# 2023-08-03_LVMi_Thermistors.net
KiCad netlist of a schematic drawn in EAGLE
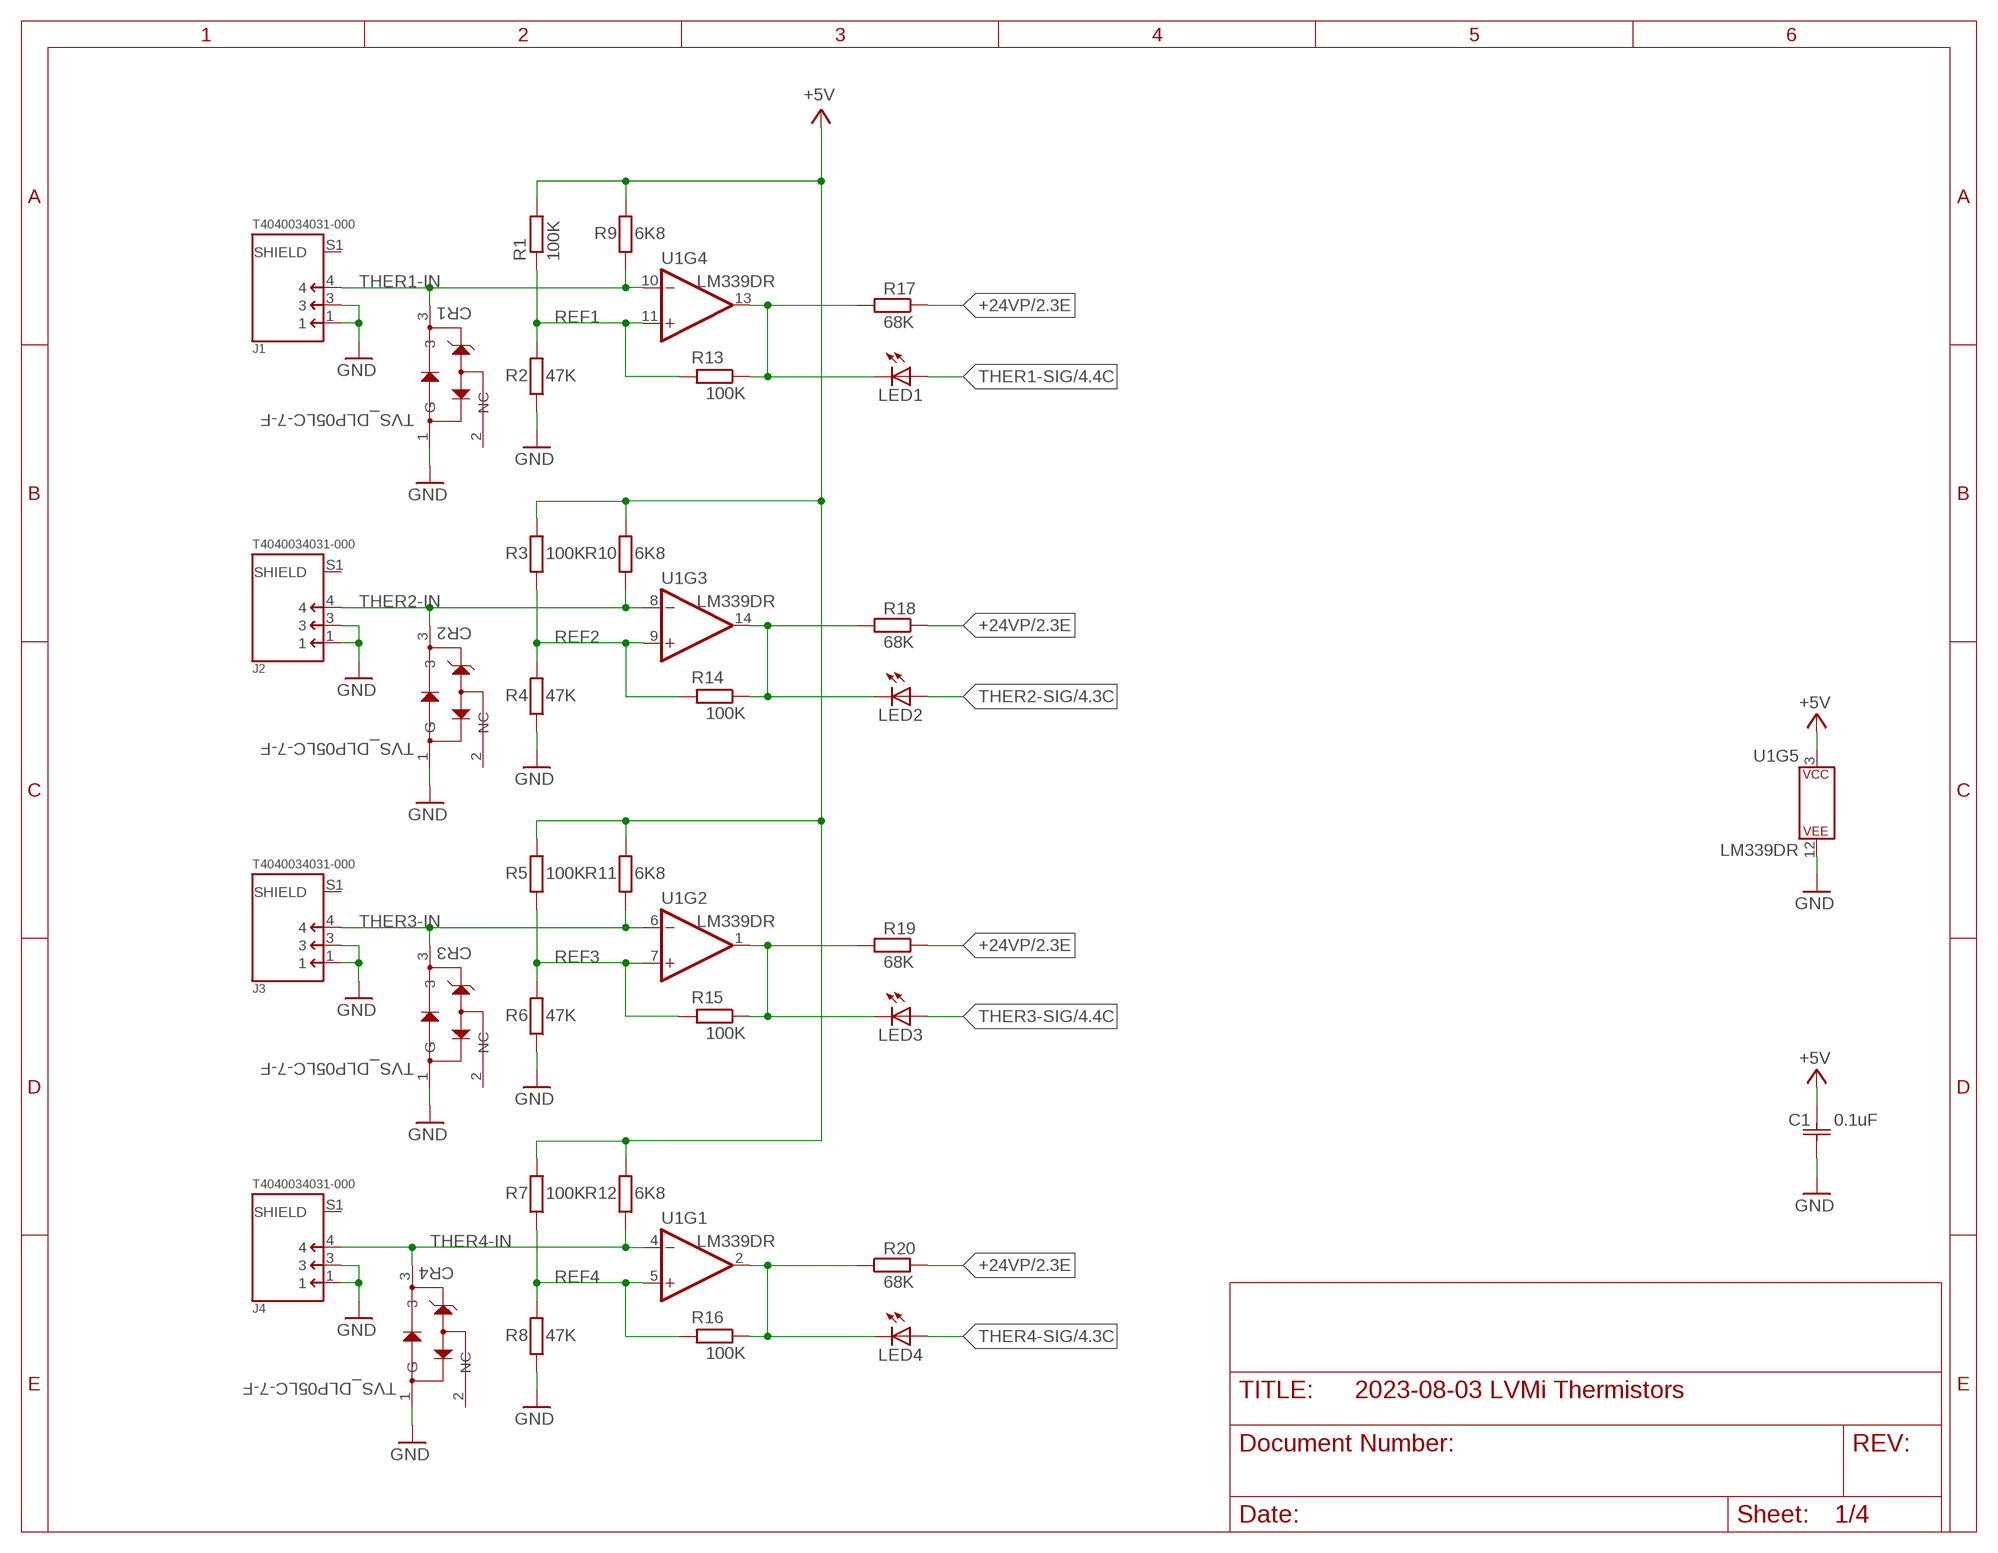
[diagram p0: schematic, sheet 1]
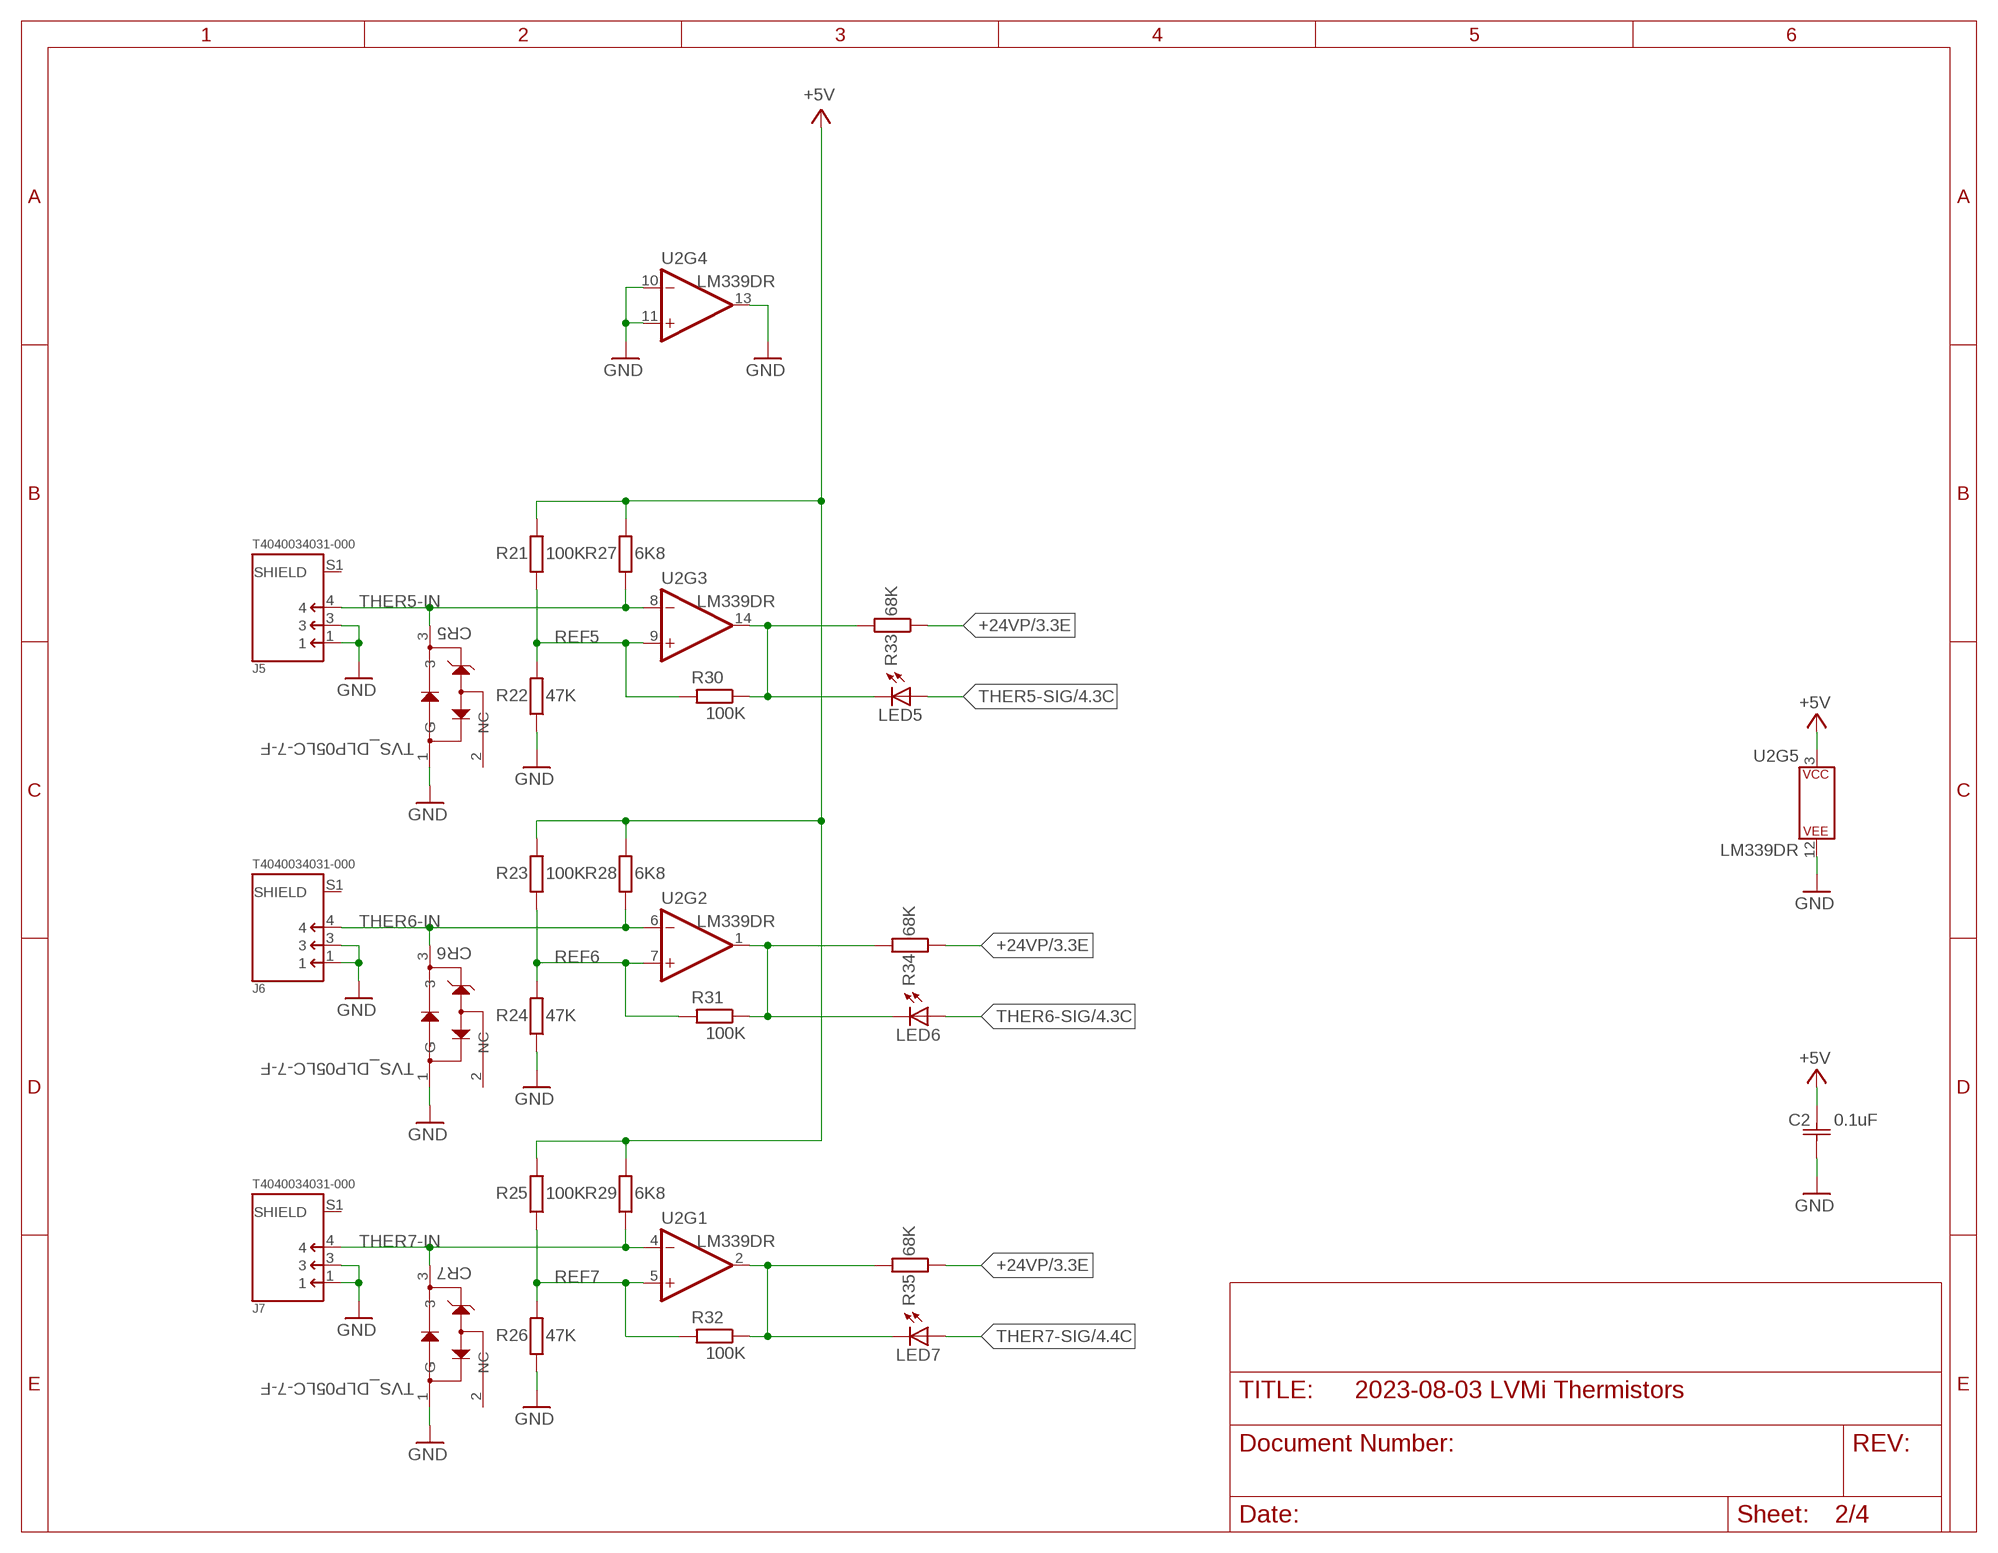
[diagram p1: schematic, sheet 2]
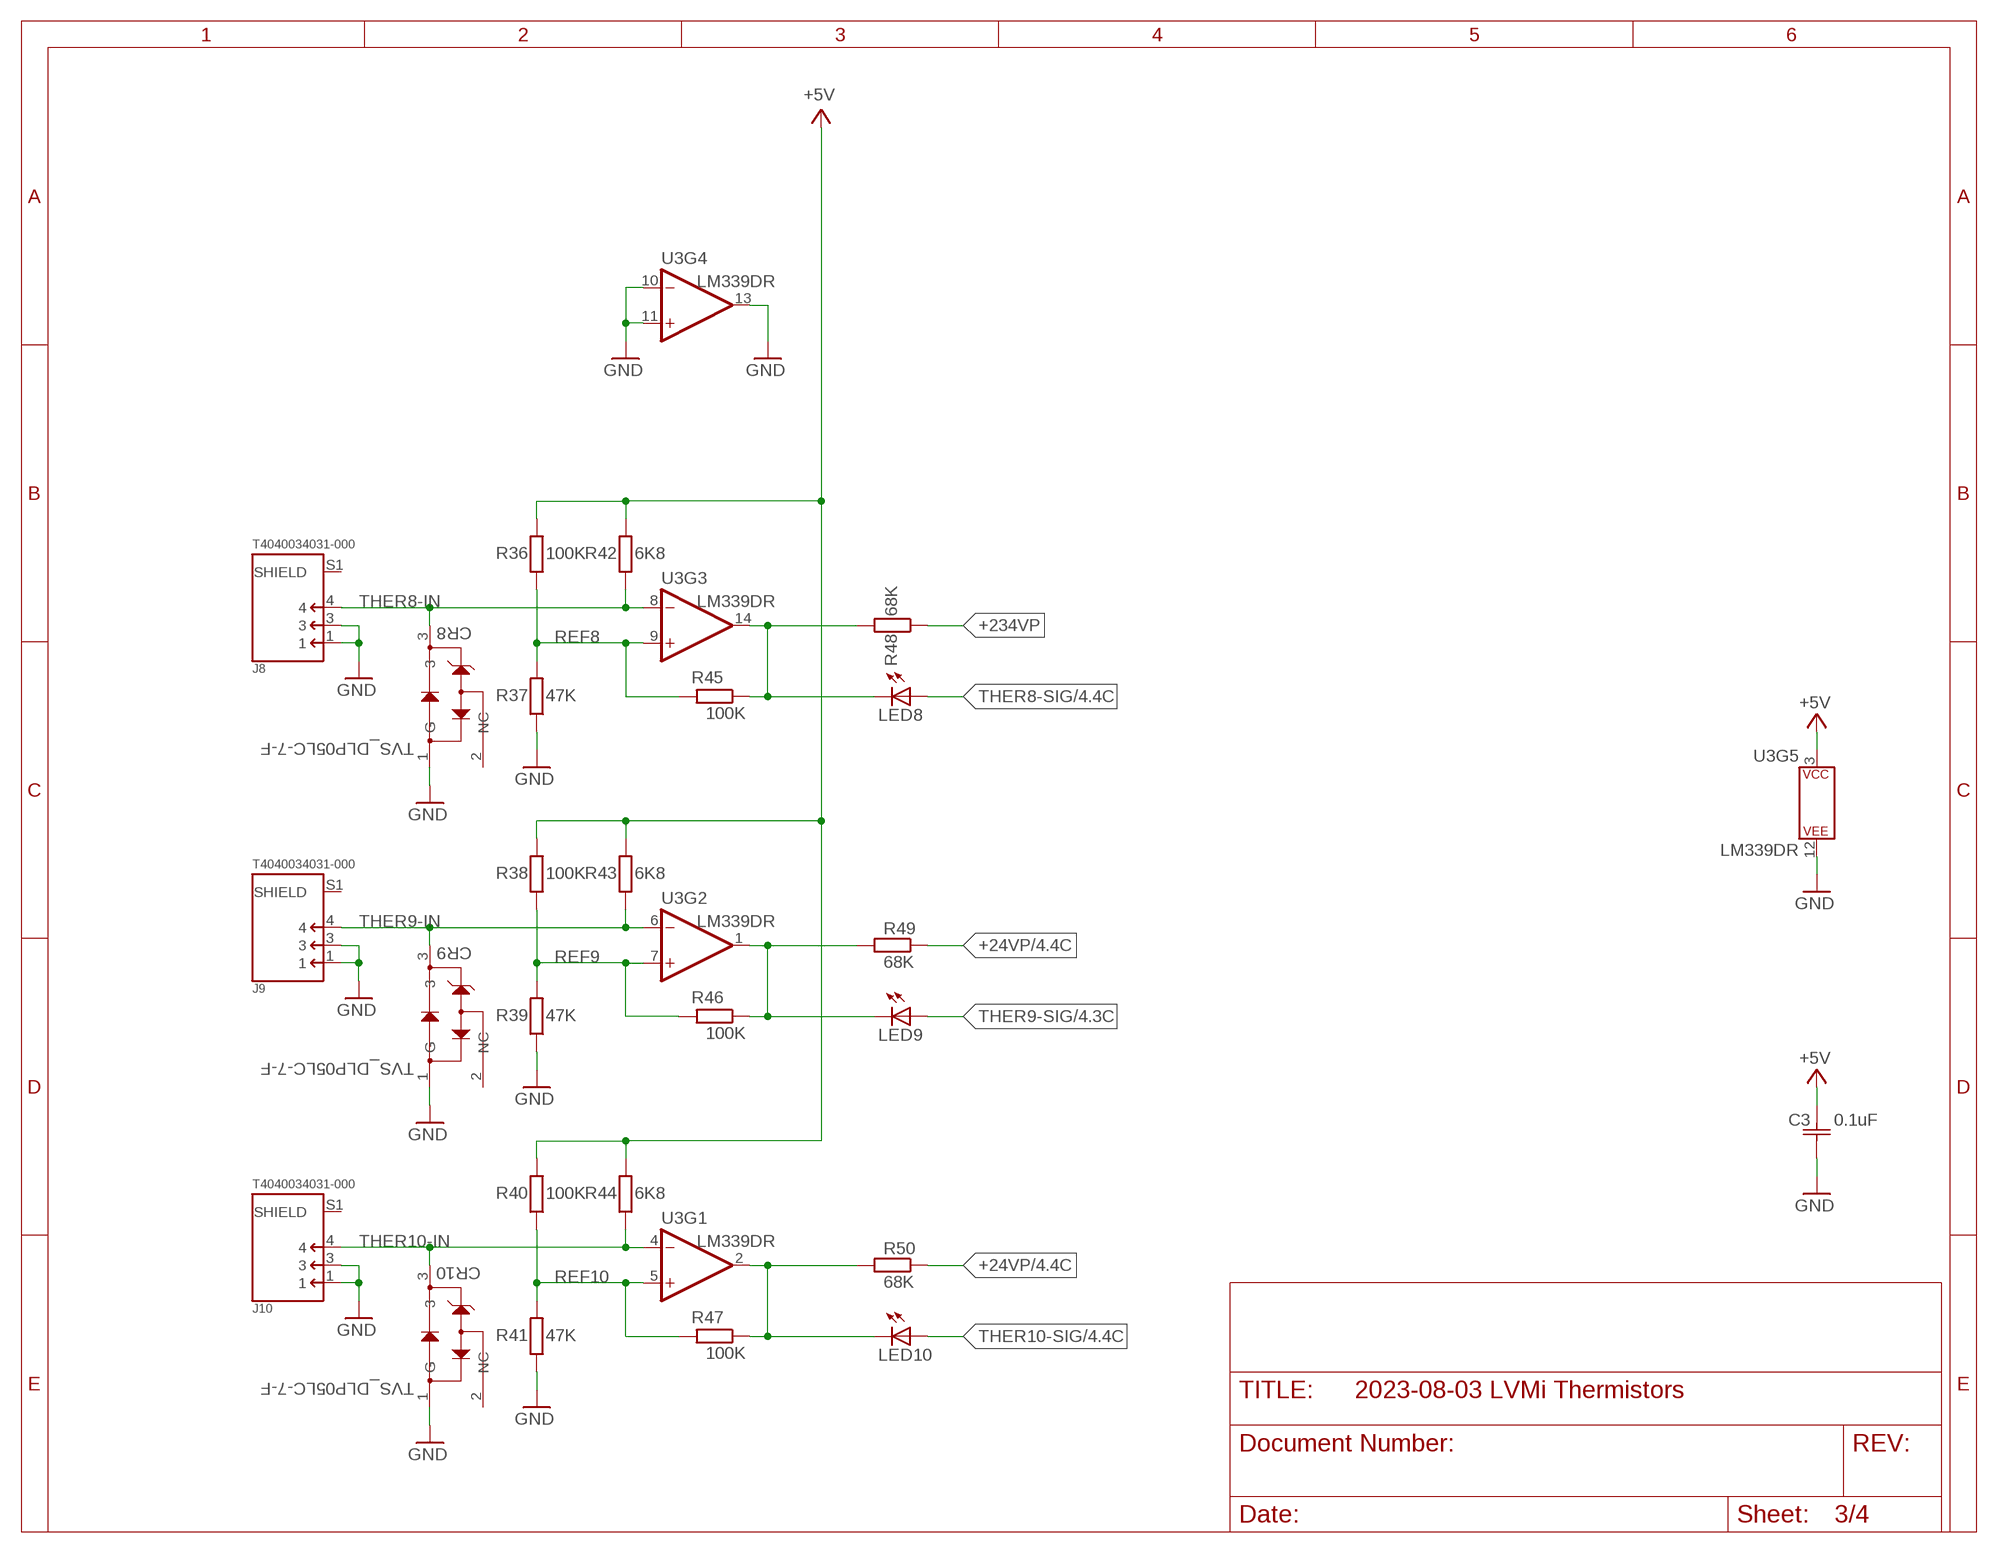
[diagram p2: schematic, sheet 3]
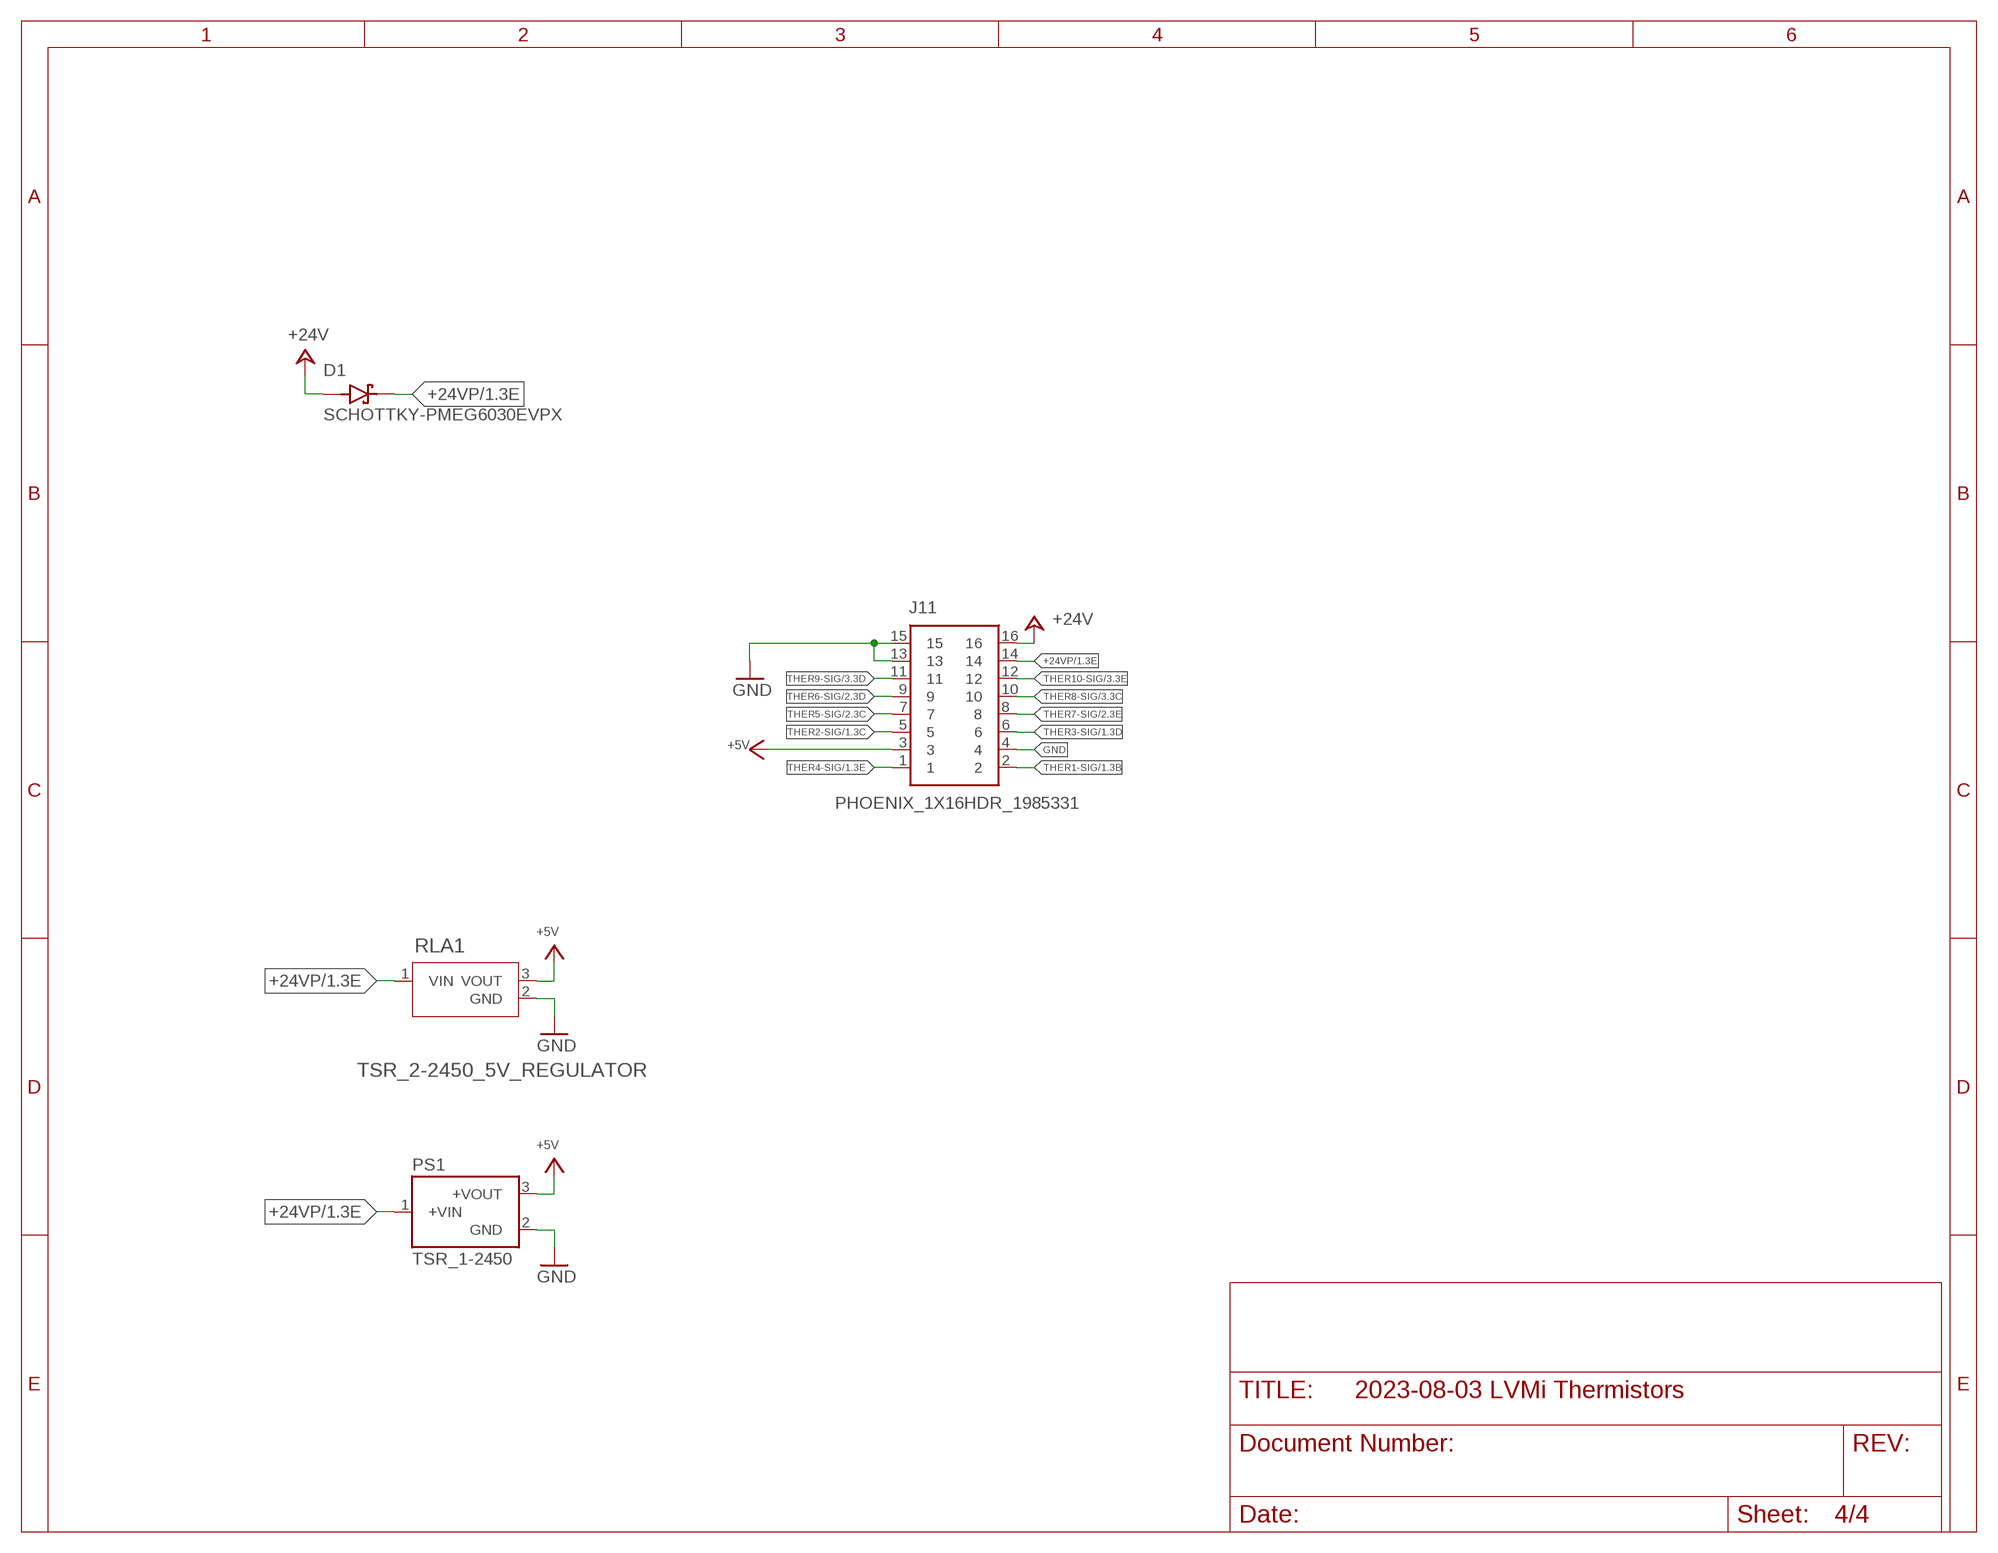
[diagram p3: schematic, sheet 4]

(export (version "E")
  (design (tool "Eeschema 10.0.6"))
  (components
    (comp (ref "C2")
      (value "0.1uF")
      (footprint "eagle-import:K104K15X7RF5TL2_VIS")
      (fields
        (field (name "MANUFACTURER_PART_NUMBER") "K104K15X7RF5TL2")
        (field (name "COPYRIGHT") "Copyright (C) 2023 Ultra Librarian. All rights reserved.")
      )
      (libsource (lib "eagle-import") (part "CAPTHRUHOLE"))
    )
    (comp (ref "CR5")
      (value "TVS_DLP05LC-7-F")
      (footprint "eagle-import:SOT23_DLP05LC_DIO")
      (fields
        (field (name "MANUFACTURER_PART_NUMBER") "DLP05LC-7-F")
        (field (name "COPYRIGHT") "Copyright (C) 2023 Ultra Librarian. All rights reserved.")
      )
      (libsource (lib "eagle-import") (part "TVS_DLP05LC-7-F"))
    )
    (comp (ref "CR6")
      (value "TVS_DLP05LC-7-F")
      (footprint "eagle-import:SOT23_DLP05LC_DIO")
      (fields
        (field (name "MANUFACTURER_PART_NUMBER") "DLP05LC-7-F")
        (field (name "COPYRIGHT") "Copyright (C) 2023 Ultra Librarian. All rights reserved.")
      )
      (libsource (lib "eagle-import") (part "TVS_DLP05LC-7-F"))
    )
    (comp (ref "CR7")
      (value "TVS_DLP05LC-7-F")
      (footprint "eagle-import:SOT23_DLP05LC_DIO")
      (fields
        (field (name "MANUFACTURER_PART_NUMBER") "DLP05LC-7-F")
        (field (name "COPYRIGHT") "Copyright (C) 2023 Ultra Librarian. All rights reserved.")
      )
      (libsource (lib "eagle-import") (part "TVS_DLP05LC-7-F"))
    )
    (comp (ref "J5")
      (value "T4040034031-000")
      (footprint "eagle-import:TE_T4040034031-000")
      (fields (field (name "MANUFACTURER") "TE "))
      (libsource (lib "eagle-import") (part "T4040034031-000"))
    )
    (comp (ref "J6")
      (value "T4040034031-000")
      (footprint "eagle-import:TE_T4040034031-000")
      (fields (field (name "MANUFACTURER") "TE "))
      (libsource (lib "eagle-import") (part "T4040034031-000"))
    )
    (comp (ref "J7")
      (value "T4040034031-000")
      (footprint "eagle-import:TE_T4040034031-000")
      (fields (field (name "MANUFACTURER") "TE "))
      (libsource (lib "eagle-import") (part "T4040034031-000"))
    )
    (comp (ref "LED5")
      (value "LED5MM")
      (footprint "eagle-import:LED5MM")
      (libsource (lib "eagle-import") (part "LED5MM"))
    )
    (comp (ref "LED6")
      (value "LED5MM")
      (footprint "eagle-import:LED5MM")
      (libsource (lib "eagle-import") (part "LED5MM"))
    )
    (comp (ref "LED7")
      (value "LED5MM")
      (footprint "eagle-import:LED5MM")
      (libsource (lib "eagle-import") (part "LED5MM"))
    )
    (comp (ref "R21")
      (value "100K")
      (footprint "eagle-import:0204_7")
      (libsource (lib "eagle-import") (part "R-EU_0204/7"))
    )
    (comp (ref "R22")
      (value "47K")
      (footprint "eagle-import:0204_7")
      (libsource (lib "eagle-import") (part "R-EU_0204/7"))
    )
    (comp (ref "R23")
      (value "100K")
      (footprint "eagle-import:0204_7")
      (libsource (lib "eagle-import") (part "R-EU_0204/7"))
    )
    (comp (ref "R24")
      (value "47K")
      (footprint "eagle-import:0204_7")
      (libsource (lib "eagle-import") (part "R-EU_0204/7"))
    )
    (comp (ref "R25")
      (value "100K")
      (footprint "eagle-import:0204_7")
      (libsource (lib "eagle-import") (part "R-EU_0204/7"))
    )
    (comp (ref "R26")
      (value "47K")
      (footprint "eagle-import:0204_7")
      (libsource (lib "eagle-import") (part "R-EU_0204/7"))
    )
    (comp (ref "R27")
      (value "6K8")
      (footprint "eagle-import:0204_7")
      (libsource (lib "eagle-import") (part "R-EU_0204/7"))
    )
    (comp (ref "R28")
      (value "6K8")
      (footprint "eagle-import:0204_7")
      (libsource (lib "eagle-import") (part "R-EU_0204/7"))
    )
    (comp (ref "R29")
      (value "6K8")
      (footprint "eagle-import:0204_7")
      (libsource (lib "eagle-import") (part "R-EU_0204/7"))
    )
    (comp (ref "R30")
      (value "100K")
      (footprint "eagle-import:0204_7")
      (libsource (lib "eagle-import") (part "R-EU_0204/7"))
    )
    (comp (ref "R31")
      (value "100K")
      (footprint "eagle-import:0204_7")
      (libsource (lib "eagle-import") (part "R-EU_0204/7"))
    )
    (comp (ref "R32")
      (value "100K")
      (footprint "eagle-import:0204_7")
      (libsource (lib "eagle-import") (part "R-EU_0204/7"))
    )
    (comp (ref "R33")
      (value "68K")
      (footprint "eagle-import:0204_7")
      (libsource (lib "eagle-import") (part "R-EU_0204/7"))
    )
    (comp (ref "R34")
      (value "68K")
      (footprint "eagle-import:0204_7")
      (libsource (lib "eagle-import") (part "R-EU_0204/7"))
    )
    (comp (ref "R35")
      (value "68K")
      (footprint "eagle-import:0204_7")
      (libsource (lib "eagle-import") (part "R-EU_0204/7"))
    )
    (comp (ref "U2")
      (value "LM339DR")
      (footprint "eagle-import:SOIC127P599X175-14")
      (libsource (lib "eagle-import") (part "LM339SOIC-14"))
    )
    (comp (ref "C1")
      (value "0.1uF")
      (footprint "eagle-import:K104K15X7RF5TL2_VIS")
      (fields
        (field (name "MANUFACTURER_PART_NUMBER") "K104K15X7RF5TL2")
        (field (name "COPYRIGHT") "Copyright (C) 2023 Ultra Librarian. All rights reserved.")
      )
      (libsource (lib "eagle-import") (part "CAPTHRUHOLE"))
    )
    (comp (ref "CR1")
      (value "TVS_DLP05LC-7-F")
      (footprint "eagle-import:SOT23_DLP05LC_DIO")
      (fields
        (field (name "MANUFACTURER_PART_NUMBER") "DLP05LC-7-F")
        (field (name "COPYRIGHT") "Copyright (C) 2023 Ultra Librarian. All rights reserved.")
      )
      (libsource (lib "eagle-import") (part "TVS_DLP05LC-7-F"))
    )
    (comp (ref "CR2")
      (value "TVS_DLP05LC-7-F")
      (footprint "eagle-import:SOT23_DLP05LC_DIO")
      (fields
        (field (name "MANUFACTURER_PART_NUMBER") "DLP05LC-7-F")
        (field (name "COPYRIGHT") "Copyright (C) 2023 Ultra Librarian. All rights reserved.")
      )
      (libsource (lib "eagle-import") (part "TVS_DLP05LC-7-F"))
    )
    (comp (ref "CR3")
      (value "TVS_DLP05LC-7-F")
      (footprint "eagle-import:SOT23_DLP05LC_DIO")
      (fields
        (field (name "MANUFACTURER_PART_NUMBER") "DLP05LC-7-F")
        (field (name "COPYRIGHT") "Copyright (C) 2023 Ultra Librarian. All rights reserved.")
      )
      (libsource (lib "eagle-import") (part "TVS_DLP05LC-7-F"))
    )
    (comp (ref "CR4")
      (value "TVS_DLP05LC-7-F")
      (footprint "eagle-import:SOT23_DLP05LC_DIO")
      (fields
        (field (name "MANUFACTURER_PART_NUMBER") "DLP05LC-7-F")
        (field (name "COPYRIGHT") "Copyright (C) 2023 Ultra Librarian. All rights reserved.")
      )
      (libsource (lib "eagle-import") (part "TVS_DLP05LC-7-F"))
    )
    (comp (ref "J1")
      (value "T4040034031-000")
      (footprint "eagle-import:TE_T4040034031-000")
      (fields (field (name "MANUFACTURER") "TE "))
      (libsource (lib "eagle-import") (part "T4040034031-000"))
    )
    (comp (ref "J2")
      (value "T4040034031-000")
      (footprint "eagle-import:TE_T4040034031-000")
      (fields (field (name "MANUFACTURER") "TE "))
      (libsource (lib "eagle-import") (part "T4040034031-000"))
    )
    (comp (ref "J3")
      (value "T4040034031-000")
      (footprint "eagle-import:TE_T4040034031-000")
      (fields (field (name "MANUFACTURER") "TE "))
      (libsource (lib "eagle-import") (part "T4040034031-000"))
    )
    (comp (ref "J4")
      (value "T4040034031-000")
      (footprint "eagle-import:TE_T4040034031-000")
      (fields (field (name "MANUFACTURER") "TE "))
      (libsource (lib "eagle-import") (part "T4040034031-000"))
    )
    (comp (ref "LED1")
      (value "LED5MM")
      (footprint "eagle-import:LED5MM")
      (libsource (lib "eagle-import") (part "LED5MM"))
    )
    (comp (ref "LED2")
      (value "LED5MM")
      (footprint "eagle-import:LED5MM")
      (libsource (lib "eagle-import") (part "LED5MM"))
    )
    (comp (ref "LED3")
      (value "LED5MM")
      (footprint "eagle-import:LED5MM")
      (libsource (lib "eagle-import") (part "LED5MM"))
    )
    (comp (ref "LED4")
      (value "LED5MM")
      (footprint "eagle-import:LED5MM")
      (libsource (lib "eagle-import") (part "LED5MM"))
    )
    (comp (ref "R1")
      (value "100K")
      (footprint "eagle-import:0204_7")
      (libsource (lib "eagle-import") (part "R-EU_0204/7"))
    )
    (comp (ref "R2")
      (value "47K")
      (footprint "eagle-import:0204_7")
      (libsource (lib "eagle-import") (part "R-EU_0204/7"))
    )
    (comp (ref "R3")
      (value "100K")
      (footprint "eagle-import:0204_7")
      (libsource (lib "eagle-import") (part "R-EU_0204/7"))
    )
    (comp (ref "R4")
      (value "47K")
      (footprint "eagle-import:0204_7")
      (libsource (lib "eagle-import") (part "R-EU_0204/7"))
    )
    (comp (ref "R5")
      (value "100K")
      (footprint "eagle-import:0204_7")
      (libsource (lib "eagle-import") (part "R-EU_0204/7"))
    )
    (comp (ref "R6")
      (value "47K")
      (footprint "eagle-import:0204_7")
      (libsource (lib "eagle-import") (part "R-EU_0204/7"))
    )
    (comp (ref "R7")
      (value "100K")
      (footprint "eagle-import:0204_7")
      (libsource (lib "eagle-import") (part "R-EU_0204/7"))
    )
    (comp (ref "R8")
      (value "47K")
      (footprint "eagle-import:0204_7")
      (libsource (lib "eagle-import") (part "R-EU_0204/7"))
    )
    (comp (ref "R9")
      (value "6K8")
      (footprint "eagle-import:0204_7")
      (libsource (lib "eagle-import") (part "R-EU_0204/7"))
    )
    (comp (ref "R10")
      (value "6K8")
      (footprint "eagle-import:0204_7")
      (libsource (lib "eagle-import") (part "R-EU_0204/7"))
    )
    (comp (ref "R11")
      (value "6K8")
      (footprint "eagle-import:0204_7")
      (libsource (lib "eagle-import") (part "R-EU_0204/7"))
    )
    (comp (ref "R12")
      (value "6K8")
      (footprint "eagle-import:0204_7")
      (libsource (lib "eagle-import") (part "R-EU_0204/7"))
    )
    (comp (ref "R13")
      (value "100K")
      (footprint "eagle-import:0204_7")
      (libsource (lib "eagle-import") (part "R-EU_0204/7"))
    )
    (comp (ref "R14")
      (value "100K")
      (footprint "eagle-import:0204_7")
      (libsource (lib "eagle-import") (part "R-EU_0204/7"))
    )
    (comp (ref "R15")
      (value "100K")
      (footprint "eagle-import:0204_7")
      (libsource (lib "eagle-import") (part "R-EU_0204/7"))
    )
    (comp (ref "R16")
      (value "100K")
      (footprint "eagle-import:0204_7")
      (libsource (lib "eagle-import") (part "R-EU_0204/7"))
    )
    (comp (ref "R17")
      (value "68K")
      (footprint "eagle-import:0204_7")
      (libsource (lib "eagle-import") (part "R-EU_0204/7"))
    )
    (comp (ref "R18")
      (value "68K")
      (footprint "eagle-import:0204_7")
      (libsource (lib "eagle-import") (part "R-EU_0204/7"))
    )
    (comp (ref "R19")
      (value "68K")
      (footprint "eagle-import:0204_7")
      (libsource (lib "eagle-import") (part "R-EU_0204/7"))
    )
    (comp (ref "R20")
      (value "68K")
      (footprint "eagle-import:0204_7")
      (libsource (lib "eagle-import") (part "R-EU_0204/7"))
    )
    (comp (ref "U1")
      (value "LM339DR")
      (footprint "eagle-import:SOIC127P599X175-14")
      (libsource (lib "eagle-import") (part "LM339SOIC-14"))
    )
    (comp (ref "C3")
      (value "0.1uF")
      (footprint "eagle-import:K104K15X7RF5TL2_VIS")
      (fields
        (field (name "MANUFACTURER_PART_NUMBER") "K104K15X7RF5TL2")
        (field (name "COPYRIGHT") "Copyright (C) 2023 Ultra Librarian. All rights reserved.")
      )
      (libsource (lib "eagle-import") (part "CAPTHRUHOLE"))
    )
    (comp (ref "CR8")
      (value "TVS_DLP05LC-7-F")
      (footprint "eagle-import:SOT23_DLP05LC_DIO")
      (fields
        (field (name "MANUFACTURER_PART_NUMBER") "DLP05LC-7-F")
        (field (name "COPYRIGHT") "Copyright (C) 2023 Ultra Librarian. All rights reserved.")
      )
      (libsource (lib "eagle-import") (part "TVS_DLP05LC-7-F"))
    )
    (comp (ref "CR9")
      (value "TVS_DLP05LC-7-F")
      (footprint "eagle-import:SOT23_DLP05LC_DIO")
      (fields
        (field (name "MANUFACTURER_PART_NUMBER") "DLP05LC-7-F")
        (field (name "COPYRIGHT") "Copyright (C) 2023 Ultra Librarian. All rights reserved.")
      )
      (libsource (lib "eagle-import") (part "TVS_DLP05LC-7-F"))
    )
    (comp (ref "CR10")
      (value "TVS_DLP05LC-7-F")
      (footprint "eagle-import:SOT23_DLP05LC_DIO")
      (fields
        (field (name "MANUFACTURER_PART_NUMBER") "DLP05LC-7-F")
        (field (name "COPYRIGHT") "Copyright (C) 2023 Ultra Librarian. All rights reserved.")
      )
      (libsource (lib "eagle-import") (part "TVS_DLP05LC-7-F"))
    )
    (comp (ref "J8")
      (value "T4040034031-000")
      (footprint "eagle-import:TE_T4040034031-000")
      (fields (field (name "MANUFACTURER") "TE "))
      (libsource (lib "eagle-import") (part "T4040034031-000"))
    )
    (comp (ref "J9")
      (value "T4040034031-000")
      (footprint "eagle-import:TE_T4040034031-000")
      (fields (field (name "MANUFACTURER") "TE "))
      (libsource (lib "eagle-import") (part "T4040034031-000"))
    )
    (comp (ref "J10")
      (value "T4040034031-000")
      (footprint "eagle-import:TE_T4040034031-000")
      (fields (field (name "MANUFACTURER") "TE "))
      (libsource (lib "eagle-import") (part "T4040034031-000"))
    )
    (comp (ref "LED8")
      (value "LED5MM")
      (footprint "eagle-import:LED5MM")
      (libsource (lib "eagle-import") (part "LED5MM"))
    )
    (comp (ref "LED9")
      (value "LED5MM")
      (footprint "eagle-import:LED5MM")
      (libsource (lib "eagle-import") (part "LED5MM"))
    )
    (comp (ref "LED10")
      (value "LED5MM")
      (footprint "eagle-import:LED5MM")
      (libsource (lib "eagle-import") (part "LED5MM"))
    )
    (comp (ref "R36")
      (value "100K")
      (footprint "eagle-import:0204_7")
      (libsource (lib "eagle-import") (part "R-EU_0204/7"))
    )
    (comp (ref "R37")
      (value "47K")
      (footprint "eagle-import:0204_7")
      (libsource (lib "eagle-import") (part "R-EU_0204/7"))
    )
    (comp (ref "R38")
      (value "100K")
      (footprint "eagle-import:0204_7")
      (libsource (lib "eagle-import") (part "R-EU_0204/7"))
    )
    (comp (ref "R39")
      (value "47K")
      (footprint "eagle-import:0204_7")
      (libsource (lib "eagle-import") (part "R-EU_0204/7"))
    )
    (comp (ref "R40")
      (value "100K")
      (footprint "eagle-import:0204_7")
      (libsource (lib "eagle-import") (part "R-EU_0204/7"))
    )
    (comp (ref "R41")
      (value "47K")
      (footprint "eagle-import:0204_7")
      (libsource (lib "eagle-import") (part "R-EU_0204/7"))
    )
    (comp (ref "R42")
      (value "6K8")
      (footprint "eagle-import:0204_7")
      (libsource (lib "eagle-import") (part "R-EU_0204/7"))
    )
    (comp (ref "R43")
      (value "6K8")
      (footprint "eagle-import:0204_7")
      (libsource (lib "eagle-import") (part "R-EU_0204/7"))
    )
    (comp (ref "R44")
      (value "6K8")
      (footprint "eagle-import:0204_7")
      (libsource (lib "eagle-import") (part "R-EU_0204/7"))
    )
    (comp (ref "R45")
      (value "100K")
      (footprint "eagle-import:0204_7")
      (libsource (lib "eagle-import") (part "R-EU_0204/7"))
    )
    (comp (ref "R46")
      (value "100K")
      (footprint "eagle-import:0204_7")
      (libsource (lib "eagle-import") (part "R-EU_0204/7"))
    )
    (comp (ref "R47")
      (value "100K")
      (footprint "eagle-import:0204_7")
      (libsource (lib "eagle-import") (part "R-EU_0204/7"))
    )
    (comp (ref "R48")
      (value "68K")
      (footprint "eagle-import:0204_7")
      (libsource (lib "eagle-import") (part "R-EU_0204/7"))
    )
    (comp (ref "R49")
      (value "68K")
      (footprint "eagle-import:0204_7")
      (libsource (lib "eagle-import") (part "R-EU_0204/7"))
    )
    (comp (ref "R50")
      (value "68K")
      (footprint "eagle-import:0204_7")
      (libsource (lib "eagle-import") (part "R-EU_0204/7"))
    )
    (comp (ref "U3")
      (value "LM339DR")
      (footprint "eagle-import:SOIC127P599X175-14")
      (libsource (lib "eagle-import") (part "LM339SOIC-14"))
    )
    (comp (ref "D1")
      (value "SCHOTTKY-PMEG6030EVPX")
      (footprint "eagle-import:DIO_PMEG6030EVPX")
      (fields
        (field (name "DIGI-KEY_PART_NUMBER") "1727-1349-1-ND")
        (field (name "MF") "Nexperia USA")
        (field (name "MP") "PMEG6030EVPX")
      )
      (libsource (lib "eagle-import") (part "SCHOTTKY-PMEG6030EVPX"))
    )
    (comp (ref "J11")
      (value "PHOENIX_1X16HDR_1985331")
      (footprint "eagle-import:1985331")
      (fields
        (field (name "MANUFACTURER_PART_NUMBER") "1985331")
        (field (name "MOUSER_PART_NUMBER") "651-1985331")
      )
      (libsource (lib "eagle-import") (part "PHOENIX_1X16HDR_1985331"))
    )
    (comp (ref "PS1")
      (value "TSR_1-2450")
      (footprint "eagle-import:CONV_TSR_1-2450")
      (fields (field (name "MANUFACTURER") "Traco Power"))
      (libsource (lib "eagle-import") (part "TSR_1-2450"))
    )
    (comp (ref "RLA1")
      (value "TSR_2-2450_5V_REGULATOR")
      (footprint "eagle-import:TSR2-SINGLE_TRP")
      (fields
        (field (name "MANUFACTURER_PART_NUMBER") "TSR 2-2450")
        (field (name "COPYRIGHT") "Copyright (C) 2022 Ultra Librarian. All rights reserved.")
      )
      (libsource (lib "eagle-import") (part "TSR_2-2450_5V_REGULATOR"))
    )
  )
  (nets
    (net (code "1") (name "+5V") (class "Default")
      (node (ref "C1") (pin "2") (pinfunction "2_2") (pintype "passive"))
      (node (ref "C2") (pin "2") (pinfunction "2_2") (pintype "passive"))
      (node (ref "C3") (pin "2") (pinfunction "2_2") (pintype "passive"))
      (node (ref "J11") (pin "3") (pinfunction "3_3") (pintype "bidirectional"))
      (node (ref "PS1") (pin "3") (pinfunction "+VOUT_3") (pintype "output"))
      (node (ref "R1") (pin "2") (pinfunction "2_2") (pintype "passive"))
      (node (ref "R10") (pin "2") (pinfunction "2_2") (pintype "passive"))
      (node (ref "R11") (pin "2") (pinfunction "2_2") (pintype "passive"))
      (node (ref "R12") (pin "2") (pinfunction "2_2") (pintype "passive"))
      (node (ref "R21") (pin "2") (pinfunction "2_2") (pintype "passive"))
      (node (ref "R23") (pin "2") (pinfunction "2_2") (pintype "passive"))
      (node (ref "R25") (pin "2") (pinfunction "2_2") (pintype "passive"))
      (node (ref "R27") (pin "2") (pinfunction "2_2") (pintype "passive"))
      (node (ref "R28") (pin "2") (pinfunction "2_2") (pintype "passive"))
      (node (ref "R29") (pin "2") (pinfunction "2_2") (pintype "passive"))
      (node (ref "R3") (pin "2") (pinfunction "2_2") (pintype "passive"))
      (node (ref "R36") (pin "2") (pinfunction "2_2") (pintype "passive"))
      (node (ref "R38") (pin "2") (pinfunction "2_2") (pintype "passive"))
      (node (ref "R40") (pin "2") (pinfunction "2_2") (pintype "passive"))
      (node (ref "R42") (pin "2") (pinfunction "2_2") (pintype "passive"))
      (node (ref "R43") (pin "2") (pinfunction "2_2") (pintype "passive"))
      (node (ref "R44") (pin "2") (pinfunction "2_2") (pintype "passive"))
      (node (ref "R5") (pin "2") (pinfunction "2_2") (pintype "passive"))
      (node (ref "R7") (pin "2") (pinfunction "2_2") (pintype "passive"))
      (node (ref "R9") (pin "2") (pinfunction "2_2") (pintype "passive"))
      (node (ref "RLA1") (pin "3") (pinfunction "VOUT_3") (pintype "passive"))
      (node (ref "U1") (pin "3") (pinfunction "P$V+_3") (pintype "bidirectional"))
      (node (ref "U2") (pin "3") (pinfunction "P$V+_3") (pintype "bidirectional"))
      (node (ref "U3") (pin "3") (pinfunction "P$V+_3") (pintype "bidirectional"))
    )
    (net (code "2") (name "+24V") (class "Default")
      (node (ref "D1") (pin "2") (pinfunction "A_2") (pintype "passive"))
      (node (ref "J11") (pin "16") (pinfunction "16_16") (pintype "bidirectional"))
    )
    (net (code "3") (name "+24VP") (class "Default")
      (node (ref "D1") (pin "1") (pinfunction "K_1") (pintype "passive"))
      (node (ref "J11") (pin "14") (pinfunction "14_14") (pintype "bidirectional"))
      (node (ref "PS1") (pin "1") (pinfunction "+VIN_1") (pintype "input"))
      (node (ref "R17") (pin "1") (pinfunction "1_1") (pintype "passive"))
      (node (ref "R18") (pin "1") (pinfunction "1_1") (pintype "passive"))
      (node (ref "R19") (pin "1") (pinfunction "1_1") (pintype "passive"))
      (node (ref "R20") (pin "2") (pinfunction "2_2") (pintype "passive"))
      (node (ref "R33") (pin "1") (pinfunction "1_1") (pintype "passive"))
      (node (ref "R34") (pin "1") (pinfunction "1_1") (pintype "passive"))
      (node (ref "R35") (pin "1") (pinfunction "1_1") (pintype "passive"))
      (node (ref "R49") (pin "1") (pinfunction "1_1") (pintype "passive"))
      (node (ref "R50") (pin "1") (pinfunction "1_1") (pintype "passive"))
      (node (ref "RLA1") (pin "1") (pinfunction "VIN_1") (pintype "passive"))
    )
    (net (code "4") (name "+234VP") (class "Default")
      (node (ref "R48") (pin "1") (pinfunction "1_1") (pintype "passive"))
    )
    (net (code "5") (name "GND") (class "Default")
      (node (ref "C1") (pin "1") (pinfunction "1_1") (pintype "passive"))
      (node (ref "C2") (pin "1") (pinfunction "1_1") (pintype "passive"))
      (node (ref "C3") (pin "1") (pinfunction "1_1") (pintype "passive"))
      (node (ref "CR1") (pin "1") (pinfunction "G_1") (pintype "passive"))
      (node (ref "CR10") (pin "1") (pinfunction "G_1") (pintype "passive"))
      (node (ref "CR2") (pin "1") (pinfunction "G_1") (pintype "passive"))
      (node (ref "CR3") (pin "1") (pinfunction "G_1") (pintype "passive"))
      (node (ref "CR4") (pin "1") (pinfunction "G_1") (pintype "passive"))
      (node (ref "CR5") (pin "1") (pinfunction "G_1") (pintype "passive"))
      (node (ref "CR6") (pin "1") (pinfunction "G_1") (pintype "passive"))
      (node (ref "CR7") (pin "1") (pinfunction "G_1") (pintype "passive"))
      (node (ref "CR8") (pin "1") (pinfunction "G_1") (pintype "passive"))
      (node (ref "CR9") (pin "1") (pinfunction "G_1") (pintype "passive"))
      (node (ref "J1") (pin "1") (pinfunction "1_1") (pintype "passive"))
      (node (ref "J1") (pin "3") (pinfunction "3_3") (pintype "passive"))
      (node (ref "J10") (pin "1") (pinfunction "1_1") (pintype "passive"))
      (node (ref "J10") (pin "3") (pinfunction "3_3") (pintype "passive"))
      (node (ref "J11") (pin "13") (pinfunction "13_13") (pintype "bidirectional"))
      (node (ref "J11") (pin "15") (pinfunction "15_15") (pintype "bidirectional"))
      (node (ref "J11") (pin "4") (pinfunction "4_4") (pintype "bidirectional"))
      (node (ref "J2") (pin "1") (pinfunction "1_1") (pintype "passive"))
      (node (ref "J2") (pin "3") (pinfunction "3_3") (pintype "passive"))
      (node (ref "J3") (pin "1") (pinfunction "1_1") (pintype "passive"))
      (node (ref "J3") (pin "3") (pinfunction "3_3") (pintype "passive"))
      (node (ref "J4") (pin "1") (pinfunction "1_1") (pintype "passive"))
      (node (ref "J4") (pin "3") (pinfunction "3_3") (pintype "passive"))
      (node (ref "J5") (pin "1") (pinfunction "1_1") (pintype "passive"))
      (node (ref "J5") (pin "3") (pinfunction "3_3") (pintype "passive"))
      (node (ref "J6") (pin "1") (pinfunction "1_1") (pintype "passive"))
      (node (ref "J6") (pin "3") (pinfunction "3_3") (pintype "passive"))
      (node (ref "J7") (pin "1") (pinfunction "1_1") (pintype "passive"))
      (node (ref "J7") (pin "3") (pinfunction "3_3") (pintype "passive"))
      (node (ref "J8") (pin "1") (pinfunction "1_1") (pintype "passive"))
      (node (ref "J8") (pin "3") (pinfunction "3_3") (pintype "passive"))
      (node (ref "J9") (pin "1") (pinfunction "1_1") (pintype "passive"))
      (node (ref "J9") (pin "3") (pinfunction "3_3") (pintype "passive"))
      (node (ref "PS1") (pin "2") (pinfunction "GND_2") (pintype "power_in"))
      (node (ref "R2") (pin "1") (pinfunction "1_1") (pintype "passive"))
      (node (ref "R22") (pin "1") (pinfunction "1_1") (pintype "passive"))
      (node (ref "R24") (pin "1") (pinfunction "1_1") (pintype "passive"))
      (node (ref "R26") (pin "1") (pinfunction "1_1") (pintype "passive"))
      (node (ref "R37") (pin "1") (pinfunction "1_1") (pintype "passive"))
      (node (ref "R39") (pin "1") (pinfunction "1_1") (pintype "passive"))
      (node (ref "R4") (pin "1") (pinfunction "1_1") (pintype "passive"))
      (node (ref "R41") (pin "1") (pinfunction "1_1") (pintype "passive"))
      (node (ref "R6") (pin "1") (pinfunction "1_1") (pintype "passive"))
      (node (ref "R8") (pin "1") (pinfunction "1_1") (pintype "passive"))
      (node (ref "RLA1") (pin "2") (pinfunction "GND_2") (pintype "passive"))
      (node (ref "U1") (pin "12") (pinfunction "P$V-_12") (pintype "bidirectional"))
      (node (ref "U2") (pin "10") (pinfunction "-IN_10") (pintype "input"))
      (node (ref "U2") (pin "11") (pinfunction "+IN_11") (pintype "input"))
      (node (ref "U2") (pin "12") (pinfunction "P$V-_12") (pintype "bidirectional"))
      (node (ref "U2") (pin "13") (pinfunction "OUT_13") (pintype "output"))
      (node (ref "U3") (pin "10") (pinfunction "-IN_10") (pintype "input"))
      (node (ref "U3") (pin "11") (pinfunction "+IN_11") (pintype "input"))
      (node (ref "U3") (pin "12") (pinfunction "P$V-_12") (pintype "bidirectional"))
      (node (ref "U3") (pin "13") (pinfunction "OUT_13") (pintype "output"))
    )
    (net (code "6") (name "REF1") (class "Default")
      (node (ref "R1") (pin "1") (pinfunction "1_1") (pintype "passive"))
      (node (ref "R13") (pin "2") (pinfunction "2_2") (pintype "passive"))
      (node (ref "R2") (pin "2") (pinfunction "2_2") (pintype "passive"))
      (node (ref "U1") (pin "11") (pinfunction "+IN_11") (pintype "input"))
    )
    (net (code "7") (name "REF2") (class "Default")
      (node (ref "R14") (pin "2") (pinfunction "2_2") (pintype "passive"))
      (node (ref "R3") (pin "1") (pinfunction "1_1") (pintype "passive"))
      (node (ref "R4") (pin "2") (pinfunction "2_2") (pintype "passive"))
      (node (ref "U1") (pin "9") (pinfunction "+IN_9") (pintype "input"))
    )
    (net (code "8") (name "REF3") (class "Default")
      (node (ref "R15") (pin "2") (pinfunction "2_2") (pintype "passive"))
      (node (ref "R5") (pin "1") (pinfunction "1_1") (pintype "passive"))
      (node (ref "R6") (pin "2") (pinfunction "2_2") (pintype "passive"))
      (node (ref "U1") (pin "7") (pinfunction "+IN_7") (pintype "input"))
    )
    (net (code "9") (name "REF4") (class "Default")
      (node (ref "R16") (pin "2") (pinfunction "2_2") (pintype "passive"))
      (node (ref "R7") (pin "1") (pinfunction "1_1") (pintype "passive"))
      (node (ref "R8") (pin "2") (pinfunction "2_2") (pintype "passive"))
      (node (ref "U1") (pin "5") (pinfunction "+IN_5") (pintype "input"))
    )
    (net (code "10") (name "REF5") (class "Default")
      (node (ref "R21") (pin "1") (pinfunction "1_1") (pintype "passive"))
      (node (ref "R22") (pin "2") (pinfunction "2_2") (pintype "passive"))
      (node (ref "R30") (pin "2") (pinfunction "2_2") (pintype "passive"))
      (node (ref "U2") (pin "9") (pinfunction "+IN_9") (pintype "input"))
    )
    (net (code "11") (name "REF6") (class "Default")
      (node (ref "R23") (pin "1") (pinfunction "1_1") (pintype "passive"))
      (node (ref "R24") (pin "2") (pinfunction "2_2") (pintype "passive"))
      (node (ref "R31") (pin "2") (pinfunction "2_2") (pintype "passive"))
      (node (ref "U2") (pin "7") (pinfunction "+IN_7") (pintype "input"))
    )
    (net (code "12") (name "REF7") (class "Default")
      (node (ref "R25") (pin "1") (pinfunction "1_1") (pintype "passive"))
      (node (ref "R26") (pin "2") (pinfunction "2_2") (pintype "passive"))
      (node (ref "R32") (pin "2") (pinfunction "2_2") (pintype "passive"))
      (node (ref "U2") (pin "5") (pinfunction "+IN_5") (pintype "input"))
    )
    (net (code "13") (name "REF8") (class "Default")
      (node (ref "R36") (pin "1") (pinfunction "1_1") (pintype "passive"))
      (node (ref "R37") (pin "2") (pinfunction "2_2") (pintype "passive"))
      (node (ref "R45") (pin "2") (pinfunction "2_2") (pintype "passive"))
      (node (ref "U3") (pin "9") (pinfunction "+IN_9") (pintype "input"))
    )
    (net (code "14") (name "REF9") (class "Default")
      (node (ref "R38") (pin "1") (pinfunction "1_1") (pintype "passive"))
      (node (ref "R39") (pin "2") (pinfunction "2_2") (pintype "passive"))
      (node (ref "R46") (pin "2") (pinfunction "2_2") (pintype "passive"))
      (node (ref "U3") (pin "7") (pinfunction "+IN_7") (pintype "input"))
    )
    (net (code "15") (name "REF10") (class "Default")
      (node (ref "R40") (pin "1") (pinfunction "1_1") (pintype "passive"))
      (node (ref "R41") (pin "2") (pinfunction "2_2") (pintype "passive"))
      (node (ref "R47") (pin "2") (pinfunction "2_2") (pintype "passive"))
      (node (ref "U3") (pin "5") (pinfunction "+IN_5") (pintype "input"))
    )
    (net (code "16") (name "THER1-IN") (class "Default")
      (node (ref "CR1") (pin "3") (pinfunction "3_3") (pintype "passive"))
      (node (ref "J1") (pin "4") (pinfunction "4_4") (pintype "passive"))
      (node (ref "LED1") (pin "K") (pinfunction "C_K") (pintype "passive"))
      (node (ref "R13") (pin "1") (pinfunction "1_1") (pintype "passive"))
      (node (ref "R17") (pin "2") (pinfunction "2_2") (pintype "passive"))
      (node (ref "R9") (pin "1") (pinfunction "1_1") (pintype "passive"))
      (node (ref "U1") (pin "10") (pinfunction "-IN_10") (pintype "input"))
      (node (ref "U1") (pin "13") (pinfunction "OUT_13") (pintype "output"))
    )
    (net (code "17") (name "THER1-SIG") (class "Default")
      (node (ref "J11") (pin "2") (pinfunction "2_2") (pintype "bidirectional"))
      (node (ref "LED1") (pin "A") (pinfunction "A_A") (pintype "passive"))
    )
    (net (code "18") (name "THER2-IN") (class "Default")
      (node (ref "CR2") (pin "3") (pinfunction "3_3") (pintype "passive"))
      (node (ref "J2") (pin "4") (pinfunction "4_4") (pintype "passive"))
      (node (ref "LED2") (pin "K") (pinfunction "C_K") (pintype "passive"))
      (node (ref "R10") (pin "1") (pinfunction "1_1") (pintype "passive"))
      (node (ref "R14") (pin "1") (pinfunction "1_1") (pintype "passive"))
      (node (ref "R18") (pin "2") (pinfunction "2_2") (pintype "passive"))
      (node (ref "U1") (pin "14") (pinfunction "OUT_14") (pintype "output"))
      (node (ref "U1") (pin "8") (pinfunction "-IN_8") (pintype "input"))
    )
    (net (code "19") (name "THER2-SIG") (class "Default")
      (node (ref "J11") (pin "5") (pinfunction "5_5") (pintype "bidirectional"))
      (node (ref "LED2") (pin "A") (pinfunction "A_A") (pintype "passive"))
    )
    (net (code "20") (name "THER3-IN") (class "Default")
      (node (ref "CR3") (pin "3") (pinfunction "3_3") (pintype "passive"))
      (node (ref "J3") (pin "4") (pinfunction "4_4") (pintype "passive"))
      (node (ref "LED3") (pin "K") (pinfunction "C_K") (pintype "passive"))
      (node (ref "R11") (pin "1") (pinfunction "1_1") (pintype "passive"))
      (node (ref "R15") (pin "1") (pinfunction "1_1") (pintype "passive"))
      (node (ref "R19") (pin "2") (pinfunction "2_2") (pintype "passive"))
      (node (ref "U1") (pin "1") (pinfunction "OUT_1") (pintype "output"))
      (node (ref "U1") (pin "6") (pinfunction "-IN_6") (pintype "input"))
    )
    (net (code "21") (name "THER3-SIG") (class "Default")
      (node (ref "J11") (pin "6") (pinfunction "6_6") (pintype "bidirectional"))
      (node (ref "LED3") (pin "A") (pinfunction "A_A") (pintype "passive"))
    )
    (net (code "22") (name "THER4-IN") (class "Default")
      (node (ref "CR4") (pin "3") (pinfunction "3_3") (pintype "passive"))
      (node (ref "J4") (pin "4") (pinfunction "4_4") (pintype "passive"))
      (node (ref "LED4") (pin "K") (pinfunction "C_K") (pintype "passive"))
      (node (ref "R12") (pin "1") (pinfunction "1_1") (pintype "passive"))
      (node (ref "R16") (pin "1") (pinfunction "1_1") (pintype "passive"))
      (node (ref "R20") (pin "1") (pinfunction "1_1") (pintype "passive"))
      (node (ref "U1") (pin "2") (pinfunction "OUT_2") (pintype "output"))
      (node (ref "U1") (pin "4") (pinfunction "-IN_4") (pintype "input"))
    )
    (net (code "23") (name "THER4-SIG") (class "Default")
      (node (ref "J11") (pin "1") (pinfunction "1_1") (pintype "bidirectional"))
      (node (ref "LED4") (pin "A") (pinfunction "A_A") (pintype "passive"))
    )
    (net (code "24") (name "THER5-IN") (class "Default")
      (node (ref "CR5") (pin "3") (pinfunction "3_3") (pintype "passive"))
      (node (ref "J5") (pin "4") (pinfunction "4_4") (pintype "passive"))
      (node (ref "LED5") (pin "K") (pinfunction "C_K") (pintype "passive"))
      (node (ref "R27") (pin "1") (pinfunction "1_1") (pintype "passive"))
      (node (ref "R30") (pin "1") (pinfunction "1_1") (pintype "passive"))
      (node (ref "R33") (pin "2") (pinfunction "2_2") (pintype "passive"))
      (node (ref "U2") (pin "14") (pinfunction "OUT_14") (pintype "output"))
      (node (ref "U2") (pin "8") (pinfunction "-IN_8") (pintype "input"))
    )
    (net (code "25") (name "THER5-SIG") (class "Default")
      (node (ref "J11") (pin "7") (pinfunction "7_7") (pintype "bidirectional"))
      (node (ref "LED5") (pin "A") (pinfunction "A_A") (pintype "passive"))
    )
    (net (code "26") (name "THER6-IN") (class "Default")
      (node (ref "CR6") (pin "3") (pinfunction "3_3") (pintype "passive"))
      (node (ref "J6") (pin "4") (pinfunction "4_4") (pintype "passive"))
      (node (ref "LED6") (pin "K") (pinfunction "C_K") (pintype "passive"))
      (node (ref "R28") (pin "1") (pinfunction "1_1") (pintype "passive"))
      (node (ref "R31") (pin "1") (pinfunction "1_1") (pintype "passive"))
      (node (ref "R34") (pin "2") (pinfunction "2_2") (pintype "passive"))
      (node (ref "U2") (pin "1") (pinfunction "OUT_1") (pintype "output"))
      (node (ref "U2") (pin "6") (pinfunction "-IN_6") (pintype "input"))
    )
    (net (code "27") (name "THER6-SIG") (class "Default")
      (node (ref "J11") (pin "9") (pinfunction "9_9") (pintype "bidirectional"))
      (node (ref "LED6") (pin "A") (pinfunction "A_A") (pintype "passive"))
    )
    (net (code "28") (name "THER7-IN") (class "Default")
      (node (ref "CR7") (pin "3") (pinfunction "3_3") (pintype "passive"))
      (node (ref "J7") (pin "4") (pinfunction "4_4") (pintype "passive"))
      (node (ref "LED7") (pin "K") (pinfunction "C_K") (pintype "passive"))
      (node (ref "R29") (pin "1") (pinfunction "1_1") (pintype "passive"))
      (node (ref "R32") (pin "1") (pinfunction "1_1") (pintype "passive"))
      (node (ref "R35") (pin "2") (pinfunction "2_2") (pintype "passive"))
      (node (ref "U2") (pin "2") (pinfunction "OUT_2") (pintype "output"))
      (node (ref "U2") (pin "4") (pinfunction "-IN_4") (pintype "input"))
    )
    (net (code "29") (name "THER7-SIG") (class "Default")
      (node (ref "J11") (pin "8") (pinfunction "8_8") (pintype "bidirectional"))
      (node (ref "LED7") (pin "A") (pinfunction "A_A") (pintype "passive"))
    )
    (net (code "30") (name "THER8-IN") (class "Default")
      (node (ref "CR8") (pin "3") (pinfunction "3_3") (pintype "passive"))
      (node (ref "J8") (pin "4") (pinfunction "4_4") (pintype "passive"))
      (node (ref "LED8") (pin "K") (pinfunction "C_K") (pintype "passive"))
      (node (ref "R42") (pin "1") (pinfunction "1_1") (pintype "passive"))
      (node (ref "R45") (pin "1") (pinfunction "1_1") (pintype "passive"))
      (node (ref "R48") (pin "2") (pinfunction "2_2") (pintype "passive"))
      (node (ref "U3") (pin "14") (pinfunction "OUT_14") (pintype "output"))
      (node (ref "U3") (pin "8") (pinfunction "-IN_8") (pintype "input"))
    )
    (net (code "31") (name "THER8-SIG") (class "Default")
      (node (ref "J11") (pin "10") (pinfunction "10_10") (pintype "bidirectional"))
      (node (ref "LED8") (pin "A") (pinfunction "A_A") (pintype "passive"))
    )
    (net (code "32") (name "THER9-IN") (class "Default")
      (node (ref "CR9") (pin "3") (pinfunction "3_3") (pintype "passive"))
      (node (ref "J9") (pin "4") (pinfunction "4_4") (pintype "passive"))
      (node (ref "LED9") (pin "K") (pinfunction "C_K") (pintype "passive"))
      (node (ref "R43") (pin "1") (pinfunction "1_1") (pintype "passive"))
      (node (ref "R46") (pin "1") (pinfunction "1_1") (pintype "passive"))
      (node (ref "R49") (pin "2") (pinfunction "2_2") (pintype "passive"))
      (node (ref "U3") (pin "1") (pinfunction "OUT_1") (pintype "output"))
      (node (ref "U3") (pin "6") (pinfunction "-IN_6") (pintype "input"))
    )
    (net (code "33") (name "THER9-SIG") (class "Default")
      (node (ref "J11") (pin "11") (pinfunction "11_11") (pintype "bidirectional"))
      (node (ref "LED9") (pin "A") (pinfunction "A_A") (pintype "passive"))
    )
    (net (code "34") (name "THER10-IN") (class "Default")
      (node (ref "CR10") (pin "3") (pinfunction "3_3") (pintype "passive"))
      (node (ref "J10") (pin "4") (pinfunction "4_4") (pintype "passive"))
      (node (ref "LED10") (pin "K") (pinfunction "C_K") (pintype "passive"))
      (node (ref "R44") (pin "1") (pinfunction "1_1") (pintype "passive"))
      (node (ref "R47") (pin "1") (pinfunction "1_1") (pintype "passive"))
      (node (ref "R50") (pin "2") (pinfunction "2_2") (pintype "passive"))
      (node (ref "U3") (pin "2") (pinfunction "OUT_2") (pintype "output"))
      (node (ref "U3") (pin "4") (pinfunction "-IN_4") (pintype "input"))
    )
    (net (code "35") (name "THER10-SIG") (class "Default")
      (node (ref "J11") (pin "12") (pinfunction "12_12") (pintype "bidirectional"))
      (node (ref "LED10") (pin "A") (pinfunction "A_A") (pintype "passive"))
    )
    (net (code "36") (name "unconnected-(CR1-NC-Pad2)") (class "Default")
      (node (ref "CR1") (pin "2") (pinfunction "NC_2") (pintype "no_connect"))
    )
    (net (code "37") (name "unconnected-(CR2-NC-Pad2)") (class "Default")
      (node (ref "CR2") (pin "2") (pinfunction "NC_2") (pintype "no_connect"))
    )
    (net (code "38") (name "unconnected-(CR3-NC-Pad2)") (class "Default")
      (node (ref "CR3") (pin "2") (pinfunction "NC_2") (pintype "no_connect"))
    )
    (net (code "39") (name "unconnected-(CR4-NC-Pad2)") (class "Default")
      (node (ref "CR4") (pin "2") (pinfunction "NC_2") (pintype "no_connect"))
    )
    (net (code "40") (name "unconnected-(CR5-NC-Pad2)") (class "Default")
      (node (ref "CR5") (pin "2") (pinfunction "NC_2") (pintype "no_connect"))
    )
    (net (code "41") (name "unconnected-(CR6-NC-Pad2)") (class "Default")
      (node (ref "CR6") (pin "2") (pinfunction "NC_2") (pintype "no_connect"))
    )
    (net (code "42") (name "unconnected-(CR7-NC-Pad2)") (class "Default")
      (node (ref "CR7") (pin "2") (pinfunction "NC_2") (pintype "no_connect"))
    )
    (net (code "43") (name "unconnected-(CR8-NC-Pad2)") (class "Default")
      (node (ref "CR8") (pin "2") (pinfunction "NC_2") (pintype "no_connect"))
    )
    (net (code "44") (name "unconnected-(CR9-NC-Pad2)") (class "Default")
      (node (ref "CR9") (pin "2") (pinfunction "NC_2") (pintype "no_connect"))
    )
    (net (code "45") (name "unconnected-(CR10-NC-Pad2)") (class "Default")
      (node (ref "CR10") (pin "2") (pinfunction "NC_2") (pintype "no_connect"))
    )
    (net (code "46") (name "unconnected-(J1-SHIELD-PadS1)") (class "Default")
      (node (ref "J1") (pin "S1") (pinfunction "SHIELD_S1") (pintype "passive"))
    )
    (net (code "47") (name "unconnected-(J2-SHIELD-PadS1)") (class "Default")
      (node (ref "J2") (pin "S1") (pinfunction "SHIELD_S1") (pintype "passive"))
    )
    (net (code "48") (name "unconnected-(J3-SHIELD-PadS1)") (class "Default")
      (node (ref "J3") (pin "S1") (pinfunction "SHIELD_S1") (pintype "passive"))
    )
    (net (code "49") (name "unconnected-(J4-SHIELD-PadS1)") (class "Default")
      (node (ref "J4") (pin "S1") (pinfunction "SHIELD_S1") (pintype "passive"))
    )
    (net (code "50") (name "unconnected-(J5-SHIELD-PadS1)") (class "Default")
      (node (ref "J5") (pin "S1") (pinfunction "SHIELD_S1") (pintype "passive"))
    )
    (net (code "51") (name "unconnected-(J6-SHIELD-PadS1)") (class "Default")
      (node (ref "J6") (pin "S1") (pinfunction "SHIELD_S1") (pintype "passive"))
    )
    (net (code "52") (name "unconnected-(J7-SHIELD-PadS1)") (class "Default")
      (node (ref "J7") (pin "S1") (pinfunction "SHIELD_S1") (pintype "passive"))
    )
    (net (code "53") (name "unconnected-(J8-SHIELD-PadS1)") (class "Default")
      (node (ref "J8") (pin "S1") (pinfunction "SHIELD_S1") (pintype "passive"))
    )
    (net (code "54") (name "unconnected-(J9-SHIELD-PadS1)") (class "Default")
      (node (ref "J9") (pin "S1") (pinfunction "SHIELD_S1") (pintype "passive"))
    )
    (net (code "55") (name "unconnected-(J10-SHIELD-PadS1)") (class "Default")
      (node (ref "J10") (pin "S1") (pinfunction "SHIELD_S1") (pintype "passive"))
    )
  )
)
